# schematic.net
KiCad netlist of a schematic drawn in Altium Designer
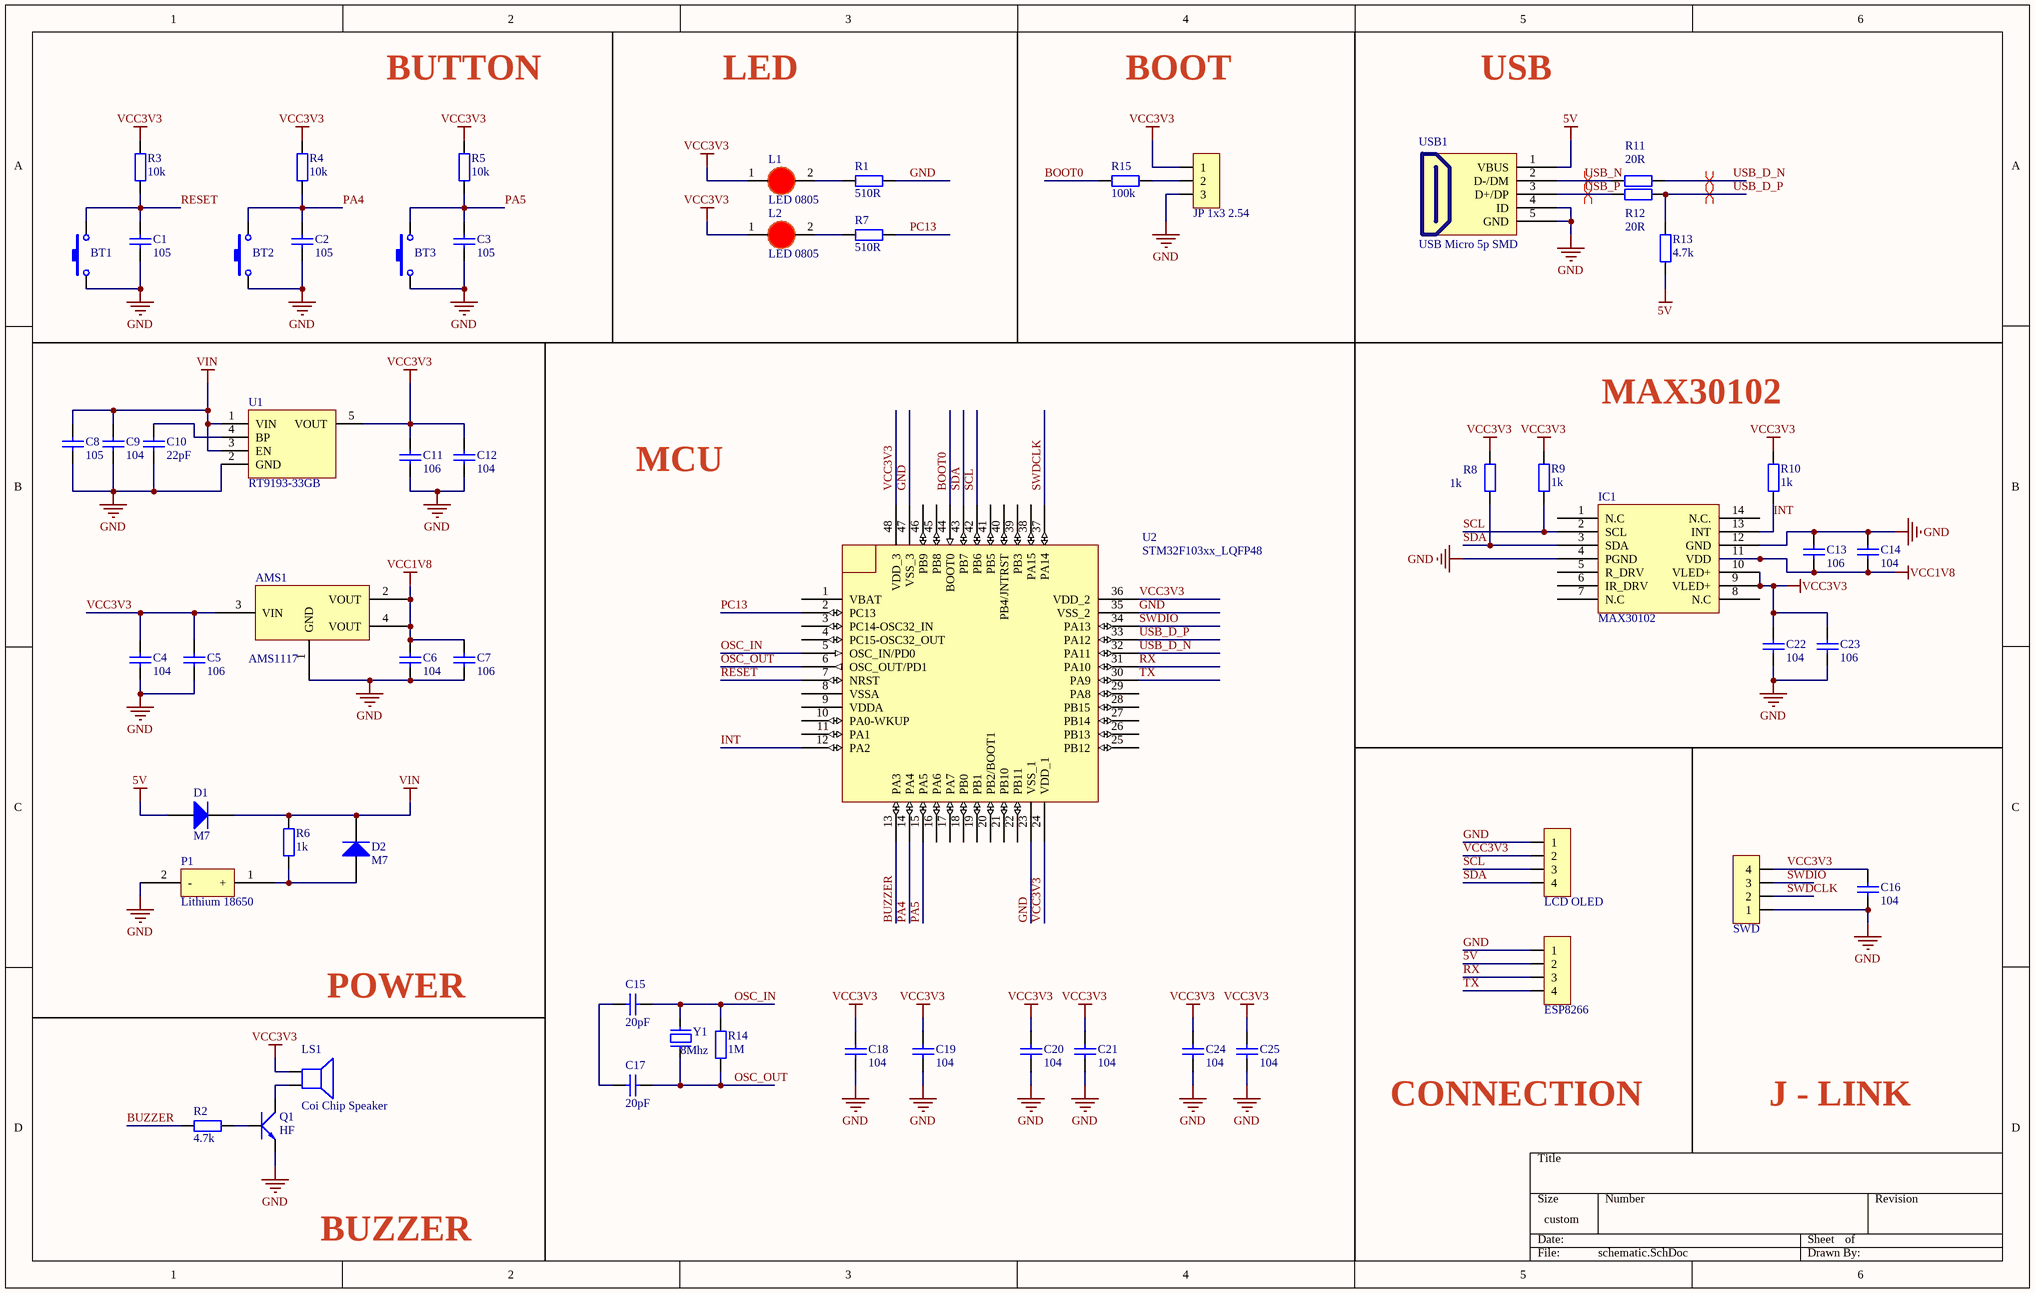
[diagram p0: schematic.SchDoc]

(export (version "E")
  (design (tool "Eeschema 10.0.6"))
  (components
    (comp (ref "AMS1")
      (value "AMS1117")
      (footprint "SOT223")
      (description "Dán")
      (libsource (lib "Altium_Lib_by_KhueNguyenCreator") (part "AMS1117 SMD"))
    )
    (comp (ref "BT1")
      (value "Nut Nhan 2 Chan SMD 3x6x2.5")
      (footprint "Nut Nhan 2 Chan SMD 3x6x2.5")
      (libsource (lib "Altium_Lib_by_KhueNguyenCreator") (part "Nut Nhan 2 Chan SMD 3x6x2.5"))
    )
    (comp (ref "BT2")
      (value "Nut Nhan 2 Chan SMD 3x6x2.5")
      (footprint "Nut Nhan 2 Chan SMD 3x6x2.5")
      (libsource (lib "Altium_Lib_by_KhueNguyenCreator") (part "Nut Nhan 2 Chan SMD 3x6x2.5"))
    )
    (comp (ref "BT3")
      (value "Nut Nhan 2 Chan SMD 3x6x2.5")
      (footprint "Nut Nhan 2 Chan SMD 3x6x2.5")
      (libsource (lib "Altium_Lib_by_KhueNguyenCreator") (part "Nut Nhan 2 Chan SMD 3x6x2.5"))
    )
    (comp (ref "C1")
      (value "105")
      (footprint "tu 0603")
      (description "Dán")
      (libsource (lib "Altium_Lib_by_KhueNguyenCreator") (part "Tu 0603 105 50V 10%"))
    )
    (comp (ref "C2")
      (value "105")
      (footprint "tu 0603")
      (description "Dán")
      (libsource (lib "Altium_Lib_by_KhueNguyenCreator") (part "Tu 0603 105 50V 10%"))
    )
    (comp (ref "C3")
      (value "105")
      (footprint "tu 0603")
      (description "Dán")
      (libsource (lib "Altium_Lib_by_KhueNguyenCreator") (part "Tu 0603 105 50V 10%"))
    )
    (comp (ref "C4")
      (value "104")
      (footprint "tu 0603")
      (description "Dán")
      (libsource (lib "Altium_Lib_by_KhueNguyenCreator") (part "Tu 0603 104 50V 10%"))
    )
    (comp (ref "C5")
      (value "106")
      (footprint "tu 0603")
      (description "Dán")
      (libsource (lib "Altium_Lib_by_KhueNguyenCreator") (part "Tu 0603 106 16V 20%"))
    )
    (comp (ref "C6")
      (value "104")
      (footprint "tu 0603")
      (description "Dán")
      (libsource (lib "Altium_Lib_by_KhueNguyenCreator") (part "Tu 0603 104 50V 10%"))
    )
    (comp (ref "C7")
      (value "106")
      (footprint "tu 0603")
      (description "Dán")
      (libsource (lib "Altium_Lib_by_KhueNguyenCreator") (part "Tu 0603 106 16V 20%"))
    )
    (comp (ref "C8")
      (value "105")
      (footprint "tu 0603")
      (description "Dán")
      (libsource (lib "Altium_Lib_by_KhueNguyenCreator") (part "Tu 0603 105 16V 20%"))
    )
    (comp (ref "C9")
      (value "104")
      (footprint "tu 0603")
      (description "Dán")
      (libsource (lib "Altium_Lib_by_KhueNguyenCreator") (part "Tu 0603 104 50V 10%"))
    )
    (comp (ref "C10")
      (value "22pF")
      (footprint "tu 0603")
      (description "Dán")
      (libsource (lib "Altium_Lib_by_KhueNguyenCreator") (part "Tu 0603 22pF 50V 10%"))
    )
    (comp (ref "C11")
      (value "106")
      (footprint "tu 0603")
      (description "Dán")
      (libsource (lib "Altium_Lib_by_KhueNguyenCreator") (part "Tu 0603 106 16V 20%"))
    )
    (comp (ref "C12")
      (value "104")
      (footprint "tu 0603")
      (description "Dán")
      (libsource (lib "Altium_Lib_by_KhueNguyenCreator") (part "Tu 0603 104 50V 10%"))
    )
    (comp (ref "C13")
      (value "106")
      (footprint "tu 0603")
      (description "Dán")
      (libsource (lib "Altium_Lib_by_KhueNguyenCreator") (part "Tu 0603 106 16V 20%"))
    )
    (comp (ref "C14")
      (value "104")
      (footprint "tu 0603")
      (description "Dán")
      (libsource (lib "Altium_Lib_by_KhueNguyenCreator") (part "Tu 0603 104 50V 10%"))
    )
    (comp (ref "C15")
      (value "20pF")
      (footprint "tu 0805")
      (description "Dán")
      (libsource (lib "Altium_Lib_by_KhueNguyenCreator") (part "Tu 0805 20pF 50V 10%"))
    )
    (comp (ref "C16")
      (value "104")
      (footprint "tu 0603")
      (description "Dán")
      (libsource (lib "Altium_Lib_by_KhueNguyenCreator") (part "Tu 0603 104 50V 10%"))
    )
    (comp (ref "C17")
      (value "20pF")
      (footprint "tu 0805")
      (description "Dán")
      (libsource (lib "Altium_Lib_by_KhueNguyenCreator") (part "Tu 0805 20pF 50V 10%"))
    )
    (comp (ref "C18")
      (value "104")
      (footprint "tu 0603")
      (description "Dán")
      (libsource (lib "Altium_Lib_by_KhueNguyenCreator") (part "Tu 0603 104 50V 10%"))
    )
    (comp (ref "C19")
      (value "104")
      (footprint "tu 0603")
      (description "Dán")
      (libsource (lib "Altium_Lib_by_KhueNguyenCreator") (part "Tu 0603 104 50V 10%"))
    )
    (comp (ref "C20")
      (value "104")
      (footprint "tu 0603")
      (description "Dán")
      (libsource (lib "Altium_Lib_by_KhueNguyenCreator") (part "Tu 0603 104 50V 10%"))
    )
    (comp (ref "C21")
      (value "104")
      (footprint "tu 0603")
      (description "Dán")
      (libsource (lib "Altium_Lib_by_KhueNguyenCreator") (part "Tu 0603 104 50V 10%"))
    )
    (comp (ref "C22")
      (value "104")
      (footprint "tu 0603")
      (description "Dán")
      (libsource (lib "Altium_Lib_by_KhueNguyenCreator") (part "Tu 0603 104 50V 10%"))
    )
    (comp (ref "C23")
      (value "106")
      (footprint "tu 0603")
      (description "Dán")
      (libsource (lib "Altium_Lib_by_KhueNguyenCreator") (part "Tu 0603 106 16V 20%"))
    )
    (comp (ref "C24")
      (value "104")
      (footprint "tu 0603")
      (description "Dán")
      (libsource (lib "Altium_Lib_by_KhueNguyenCreator") (part "Tu 0603 104 50V 10%"))
    )
    (comp (ref "C25")
      (value "104")
      (footprint "tu 0603")
      (description "Dán")
      (libsource (lib "Altium_Lib_by_KhueNguyenCreator") (part "Tu 0603 104 50V 10%"))
    )
    (comp (ref "D1")
      (value "M7")
      (footprint "DIODE SMA")
      (description "Dán")
      (libsource (lib "Altium_Lib_by_KhueNguyenCreator") (part "Diode M7 ( 4007 )"))
    )
    (comp (ref "D2")
      (value "M7")
      (footprint "DIODE SMA")
      (description "Dán")
      (libsource (lib "Altium_Lib_by_KhueNguyenCreator") (part "Diode M7 ( 4007 )"))
    )
    (comp (ref "IC1") (value "MAX30102") (footprint "Max30102") (libsource (lib "MyLib") (part "MAX30102")))
    (comp (ref "JP1")
      (value "SWD")
      (footprint "JP 1x4 DT")
      (description "Cắm")
      (libsource (lib "") (part "JP 1x4 2.54 Duc Thang_1"))
    )
    (comp (ref "JP2")
      (value "LCD OLED")
      (footprint "JP 1x4 DT")
      (description "Cắm")
      (libsource (lib "Altium_Lib_by_KhueNguyenCreator") (part "JP 1x4 2.54 Duc Thang"))
    )
    (comp (ref "JP3")
      (value "JP 1x3 2.54")
      (footprint "JP 1x3 DT")
      (description "Cắm")
      (libsource (lib "Altium_Lib_by_KhueNguyenCreator") (part "JP 1x3 2.54 Duc Thang"))
    )
    (comp (ref "JP4")
      (value "ESP8266")
      (footprint "JP 1x4 DT")
      (description "Cắm")
      (libsource (lib "Altium_Lib_by_KhueNguyenCreator") (part "JP 1x4 2.54 Duc Thang"))
    )
    (comp (ref "L1")
      (value "LED 0805")
      (footprint "LED-0805-Red")
      (description "Dán")
      (libsource (lib "Altium_Lib_by_KhueNguyenCreator") (part "LED 0805 Do"))
    )
    (comp (ref "L2")
      (value "LED 0805")
      (footprint "LED-0805-Red")
      (description "Dán")
      (libsource (lib "Altium_Lib_by_KhueNguyenCreator") (part "LED 0805 Do"))
    )
    (comp (ref "LS1")
      (value "Coi Chip Speaker")
      (footprint "Coi Chip Speacker")
      (description "Còi chip")
      (libsource (lib "Altium_Lib_by_KhueNguyenCreator") (part "Coi Chip Speaker"))
    )
    (comp (ref "P1")
      (value "Lithium 18650")
      (footprint "18650_Lithium")
      (libsource (lib "MyLib") (part "Lithium 18650"))
    )
    (comp (ref "Q1")
      (value "HF")
      (footprint "SOT-23")
      (description "SOT-23")
      (libsource (lib "Altium_Lib_by_KhueNguyenCreator") (part "Trans C1815 HF SMD"))
    )
    (comp (ref "R1")
      (value "510R")
      (footprint "tro smd 0603")
      (description "Dán")
      (libsource (lib "Altium_Lib_by_KhueNguyenCreator") (part "Tro 0603 5% 510R"))
    )
    (comp (ref "R2")
      (value "4.7k")
      (footprint "tro smd 0603")
      (description "Dán")
      (libsource (lib "Altium_Lib_by_KhueNguyenCreator") (part "Tro 0603 5% 4.7k"))
    )
    (comp (ref "R3")
      (value "10k")
      (footprint "tro smd 0603")
      (description "Dán")
      (libsource (lib "Altium_Lib_by_KhueNguyenCreator") (part "Tro 0603 1% 10k"))
    )
    (comp (ref "R4")
      (value "10k")
      (footprint "tro smd 0603")
      (description "Dán")
      (libsource (lib "Altium_Lib_by_KhueNguyenCreator") (part "Tro 0603 1% 10k"))
    )
    (comp (ref "R5")
      (value "10k")
      (footprint "tro smd 0603")
      (description "Dán")
      (libsource (lib "Altium_Lib_by_KhueNguyenCreator") (part "Tro 0603 1% 10k"))
    )
    (comp (ref "R6")
      (value "1k")
      (footprint "tro smd 0603")
      (description "Dán")
      (libsource (lib "Altium_Lib_by_KhueNguyenCreator") (part "Tro 0603 5% 1k"))
    )
    (comp (ref "R7")
      (value "510R")
      (footprint "tro smd 0603")
      (description "Dán")
      (libsource (lib "Altium_Lib_by_KhueNguyenCreator") (part "Tro 0603 5% 510R"))
    )
    (comp (ref "R8")
      (value "1k")
      (footprint "tro smd 0603")
      (description "Dán")
      (libsource (lib "Altium_Lib_by_KhueNguyenCreator") (part "Tro 0603 5% 4.7k"))
    )
    (comp (ref "R9")
      (value "1k")
      (footprint "tro smd 0603")
      (description "Dán")
      (libsource (lib "Altium_Lib_by_KhueNguyenCreator") (part "Tro 0603 5% 4.7k"))
    )
    (comp (ref "R10")
      (value "1k")
      (footprint "tro smd 0603")
      (description "Dán")
      (libsource (lib "Altium_Lib_by_KhueNguyenCreator") (part "Tro 0603 5% 4.7k"))
    )
    (comp (ref "R11")
      (value "20R")
      (footprint "tro smd 0603")
      (description "Dán")
      (libsource (lib "Altium_Lib_by_KhueNguyenCreator") (part "Tro 0603 5% 22R"))
    )
    (comp (ref "R12")
      (value "20R")
      (footprint "tro smd 0603")
      (description "Dán")
      (libsource (lib "Altium_Lib_by_KhueNguyenCreator") (part "Tro 0603 5% 22R"))
    )
    (comp (ref "R13")
      (value "4.7k")
      (footprint "tro smd 0603")
      (description "Dán")
      (libsource (lib "Altium_Lib_by_KhueNguyenCreator") (part "Tro 0603 5% 4.7k"))
    )
    (comp (ref "R14")
      (value "1M")
      (footprint "tro smd 0603")
      (description "Dán")
      (libsource (lib "Altium_Lib_by_KhueNguyenCreator") (part "Tro 0603 5% 1M"))
    )
    (comp (ref "R15")
      (value "100k")
      (footprint "tro smd 0603")
      (description "Dán")
      (libsource (lib "Altium_Lib_by_KhueNguyenCreator") (part "Tro 0603 5% 100k"))
    )
    (comp (ref "U1")
      (value "RT9193-33GB")
      (footprint "SOT23-5")
      (description "Linear Voltage Regulator IC 1 Output 300mA SOT-23-5")
      (fields (field (name "MANUFACTURER") "Richtek USA Inc."))
      (libsource (lib "Altium_Lib_by_KhueNguyenCreator") (part "REG_5.5V-3.3V-0.3A-1W-SOT-23-5"))
    )
    (comp (ref "U2")
      (value "STM32F103xx_LQFP48")
      (footprint "STM32_LQPF48")
      (fields (field (name "PUBLISHER") "Altium Limited"))
      (libsource (lib "Altium_Lib_by_KhueNguyenCreator") (part "STM32F103xx_LQFP48"))
    )
    (comp (ref "USB1")
      (value "USB Micro 5p SMD")
      (footprint "USB Micro 5p SMD")
      (description "USB Type B")
      (libsource (lib "Altium_Lib_by_KhueNguyenCreator") (part "USB Micro 5p SMD"))
    )
    (comp (ref "Y1")
      (value "8Mhz")
      (footprint "Thach Anh 2 chan SMD5032")
      (description "Crystal For all Crystal 2pin.")
      (libsource (lib "Altium_Lib_by_KhueNguyenCreator") (part "Thach Anh 2 chan SMD 5032"))
    )
  )
  (nets
    (net (code "1") (name "/BOOT0") (class "Default")
      (node (ref "R15") (pin "1") (pinfunction "1_1") (pintype "passive"))
      (node (ref "U2") (pin "44") (pinfunction "BOOT0_44") (pintype "input"))
    )
    (net (code "2") (name "/BUZZER") (class "Default")
      (node (ref "R2") (pin "1") (pinfunction "1_1") (pintype "passive"))
      (node (ref "U2") (pin "13") (pinfunction "PA3_13") (pintype "bidirectional"))
    )
    (net (code "3") (name "/INT") (class "Default")
      (node (ref "IC1") (pin "13") (pinfunction "INT_13") (pintype "passive"))
      (node (ref "R10") (pin "2") (pinfunction "2_2") (pintype "passive"))
      (node (ref "U2") (pin "12") (pinfunction "PA2_12") (pintype "bidirectional"))
    )
    (net (code "4") (name "/OSC_IN") (class "Default")
      (node (ref "C15") (pin "1") (pinfunction "1_1") (pintype "passive"))
      (node (ref "R14") (pin "2") (pinfunction "2_2") (pintype "passive"))
      (node (ref "U2") (pin "5") (pinfunction "OSC_IN/PD0_5") (pintype "input"))
      (node (ref "Y1") (pin "2") (pinfunction "2_2") (pintype "passive"))
    )
    (net (code "5") (name "/OSC_OUT") (class "Default")
      (node (ref "C17") (pin "1") (pinfunction "1_1") (pintype "passive"))
      (node (ref "R14") (pin "1") (pinfunction "1_1") (pintype "passive"))
      (node (ref "U2") (pin "6") (pinfunction "OSC_OUT/PD1_6") (pintype "output"))
      (node (ref "Y1") (pin "1") (pinfunction "1_1") (pintype "passive"))
    )
    (net (code "6") (name "/PA4") (class "Default")
      (node (ref "BT2") (pin "2") (pinfunction "2_2") (pintype "passive"))
      (node (ref "C2") (pin "1") (pinfunction "1_1") (pintype "passive"))
      (node (ref "R4") (pin "1") (pinfunction "1_1") (pintype "passive"))
      (node (ref "U2") (pin "14") (pinfunction "PA4_14") (pintype "bidirectional"))
    )
    (net (code "7") (name "/PA5") (class "Default")
      (node (ref "BT3") (pin "2") (pinfunction "2_2") (pintype "passive"))
      (node (ref "C3") (pin "1") (pinfunction "1_1") (pintype "passive"))
      (node (ref "R5") (pin "1") (pinfunction "1_1") (pintype "passive"))
      (node (ref "U2") (pin "15") (pinfunction "PA5_15") (pintype "bidirectional"))
    )
    (net (code "8") (name "/PC13") (class "Default")
      (node (ref "R7") (pin "2") (pinfunction "2_2") (pintype "passive"))
      (node (ref "U2") (pin "2") (pinfunction "PC13_2") (pintype "bidirectional"))
    )
    (net (code "9") (name "/RESET") (class "Default")
      (node (ref "BT1") (pin "2") (pinfunction "2_2") (pintype "passive"))
      (node (ref "C1") (pin "1") (pinfunction "1_1") (pintype "passive"))
      (node (ref "R3") (pin "1") (pinfunction "1_1") (pintype "passive"))
      (node (ref "U2") (pin "7") (pinfunction "NRST_7") (pintype "bidirectional"))
    )
    (net (code "10") (name "/RX") (class "Default")
      (node (ref "JP4") (pin "3") (pinfunction "3_3") (pintype "passive"))
      (node (ref "U2") (pin "31") (pinfunction "PA10_31") (pintype "bidirectional"))
    )
    (net (code "11") (name "/SCL") (class "Default")
      (node (ref "IC1") (pin "2") (pinfunction "SCL_2") (pintype "passive"))
      (node (ref "JP2") (pin "3") (pinfunction "3_3") (pintype "passive"))
      (node (ref "R9") (pin "2") (pinfunction "2_2") (pintype "passive"))
      (node (ref "U2") (pin "42") (pinfunction "PB6_42") (pintype "bidirectional"))
    )
    (net (code "12") (name "/SDA") (class "Default")
      (node (ref "IC1") (pin "3") (pinfunction "SDA_3") (pintype "passive"))
      (node (ref "JP2") (pin "4") (pinfunction "4_4") (pintype "passive"))
      (node (ref "R8") (pin "1") (pinfunction "1_1") (pintype "passive"))
      (node (ref "U2") (pin "43") (pinfunction "PB7_43") (pintype "bidirectional"))
    )
    (net (code "13") (name "/SWDCLK") (class "Default")
      (node (ref "JP1") (pin "2") (pinfunction "2_2") (pintype "passive"))
      (node (ref "U2") (pin "37") (pinfunction "PA14_37") (pintype "bidirectional"))
    )
    (net (code "14") (name "/SWDIO") (class "Default")
      (node (ref "JP1") (pin "3") (pinfunction "3_3") (pintype "passive"))
      (node (ref "U2") (pin "34") (pinfunction "PA13_34") (pintype "bidirectional"))
    )
    (net (code "15") (name "/TX") (class "Default")
      (node (ref "JP4") (pin "4") (pinfunction "4_4") (pintype "passive"))
      (node (ref "U2") (pin "30") (pinfunction "PA9_30") (pintype "bidirectional"))
    )
    (net (code "16") (name "/USB_D_N") (class "Default")
      (node (ref "R11") (pin "2") (pinfunction "2_2") (pintype "passive"))
      (node (ref "U2") (pin "32") (pinfunction "PA11_32") (pintype "bidirectional"))
    )
    (net (code "17") (name "/USB_D_P") (class "Default")
      (node (ref "R12") (pin "2") (pinfunction "2_2") (pintype "passive"))
      (node (ref "R13") (pin "2") (pinfunction "2_2") (pintype "passive"))
      (node (ref "U2") (pin "33") (pinfunction "PA12_33") (pintype "bidirectional"))
    )
    (net (code "18") (name "/USB_N") (class "Default")
      (node (ref "R11") (pin "1") (pinfunction "1_1") (pintype "passive"))
      (node (ref "USB1") (pin "2") (pinfunction "D-/DM_2") (pintype "passive"))
    )
    (net (code "19") (name "/USB_P") (class "Default")
      (node (ref "R12") (pin "1") (pinfunction "1_1") (pintype "passive"))
      (node (ref "USB1") (pin "3") (pinfunction "D+/DP_3") (pintype "passive"))
    )
    (net (code "20") (name "5V") (class "Default")
      (node (ref "D1") (pin "1") (pinfunction "A_1") (pintype "passive"))
      (node (ref "JP4") (pin "2") (pinfunction "2_2") (pintype "passive"))
      (node (ref "R13") (pin "1") (pinfunction "1_1") (pintype "passive"))
      (node (ref "USB1") (pin "1") (pinfunction "VBUS_1") (pintype "passive"))
    )
    (net (code "21") (name "GND") (class "Default")
      (node (ref "AMS1") (pin "1") (pinfunction "GND_1") (pintype "passive"))
      (node (ref "BT1") (pin "1") (pinfunction "1_1") (pintype "passive"))
      (node (ref "BT2") (pin "1") (pinfunction "1_1") (pintype "passive"))
      (node (ref "BT3") (pin "1") (pinfunction "1_1") (pintype "passive"))
      (node (ref "C1") (pin "2") (pinfunction "2_2") (pintype "passive"))
      (node (ref "C10") (pin "2") (pinfunction "2_2") (pintype "passive"))
      (node (ref "C11") (pin "2") (pinfunction "2_2") (pintype "passive"))
      (node (ref "C12") (pin "2") (pinfunction "2_2") (pintype "passive"))
      (node (ref "C13") (pin "1") (pinfunction "1_1") (pintype "passive"))
      (node (ref "C14") (pin "1") (pinfunction "1_1") (pintype "passive"))
      (node (ref "C16") (pin "2") (pinfunction "2_2") (pintype "passive"))
      (node (ref "C18") (pin "2") (pinfunction "2_2") (pintype "passive"))
      (node (ref "C19") (pin "2") (pinfunction "2_2") (pintype "passive"))
      (node (ref "C2") (pin "2") (pinfunction "2_2") (pintype "passive"))
      (node (ref "C20") (pin "2") (pinfunction "2_2") (pintype "passive"))
      (node (ref "C21") (pin "2") (pinfunction "2_2") (pintype "passive"))
      (node (ref "C22") (pin "1") (pinfunction "1_1") (pintype "passive"))
      (node (ref "C23") (pin "1") (pinfunction "1_1") (pintype "passive"))
      (node (ref "C24") (pin "2") (pinfunction "2_2") (pintype "passive"))
      (node (ref "C25") (pin "2") (pinfunction "2_2") (pintype "passive"))
      (node (ref "C3") (pin "2") (pinfunction "2_2") (pintype "passive"))
      (node (ref "C4") (pin "1") (pinfunction "1_1") (pintype "passive"))
      (node (ref "C5") (pin "1") (pinfunction "1_1") (pintype "passive"))
      (node (ref "C6") (pin "1") (pinfunction "1_1") (pintype "passive"))
      (node (ref "C7") (pin "1") (pinfunction "1_1") (pintype "passive"))
      (node (ref "C8") (pin "2") (pinfunction "2_2") (pintype "passive"))
      (node (ref "C9") (pin "2") (pinfunction "2_2") (pintype "passive"))
      (node (ref "IC1") (pin "12") (pinfunction "GND_12") (pintype "passive"))
      (node (ref "IC1") (pin "4") (pinfunction "PGND_4") (pintype "passive"))
      (node (ref "JP1") (pin "1") (pinfunction "1_1") (pintype "passive"))
      (node (ref "JP2") (pin "1") (pinfunction "1_1") (pintype "passive"))
      (node (ref "JP3") (pin "3") (pinfunction "3_3") (pintype "passive"))
      (node (ref "JP4") (pin "1") (pinfunction "1_1") (pintype "passive"))
      (node (ref "P1") (pin "2") (pinfunction "-_2") (pintype "power_in"))
      (node (ref "Q1") (pin "2") (pinfunction "E_2") (pintype "passive"))
      (node (ref "R1") (pin "2") (pinfunction "2_2") (pintype "passive"))
      (node (ref "U1") (pin "2") (pinfunction "GND_2") (pintype "passive"))
      (node (ref "U2") (pin "23") (pinfunction "VSS_1_23") (pintype "power_in"))
      (node (ref "U2") (pin "35") (pinfunction "VSS_2_35") (pintype "power_in"))
      (node (ref "U2") (pin "47") (pinfunction "VSS_3_47") (pintype "power_in"))
      (node (ref "USB1") (pin "4") (pinfunction "ID_4") (pintype "passive"))
      (node (ref "USB1") (pin "5") (pinfunction "GND_5") (pintype "passive"))
    )
    (net (code "22") (name "Net-(C15-Pad2)") (class "Default")
      (node (ref "C15") (pin "2") (pinfunction "2_2") (pintype "passive"))
      (node (ref "C17") (pin "2") (pinfunction "2_2") (pintype "passive"))
    )
    (net (code "23") (name "Net-(D2-A)") (class "Default")
      (node (ref "D2") (pin "1") (pinfunction "A_1") (pintype "passive"))
      (node (ref "P1") (pin "1") (pinfunction "+_1") (pintype "passive"))
      (node (ref "R6") (pin "1") (pinfunction "1_1") (pintype "passive"))
    )
    (net (code "24") (name "Net-(JP3-Pad2)") (class "Default")
      (node (ref "JP3") (pin "2") (pinfunction "2_2") (pintype "passive"))
      (node (ref "R15") (pin "2") (pinfunction "2_2") (pintype "passive"))
    )
    (net (code "25") (name "Net-(L1-K)") (class "Default")
      (node (ref "L1") (pin "2") (pinfunction "K_2") (pintype "passive"))
      (node (ref "R1") (pin "1") (pinfunction "1_1") (pintype "passive"))
    )
    (net (code "26") (name "Net-(L2-K)") (class "Default")
      (node (ref "L2") (pin "2") (pinfunction "K_2") (pintype "passive"))
      (node (ref "R7") (pin "1") (pinfunction "1_1") (pintype "passive"))
    )
    (net (code "27") (name "Net-(Q1-B)") (class "Default")
      (node (ref "Q1") (pin "1") (pinfunction "B_1") (pintype "passive"))
      (node (ref "R2") (pin "2") (pinfunction "2_2") (pintype "passive"))
    )
    (net (code "28") (name "Net-(Q1-C)") (class "Default")
      (node (ref "LS1") (pin "2") (pinfunction "2_2") (pintype "passive"))
      (node (ref "Q1") (pin "3") (pinfunction "C_3") (pintype "passive"))
    )
    (net (code "29") (name "Net-(U1-BP)") (class "Default")
      (node (ref "C10") (pin "1") (pinfunction "1_1") (pintype "passive"))
      (node (ref "U1") (pin "4") (pinfunction "BP_4") (pintype "passive"))
    )
    (net (code "30") (name "VCC1V8") (class "Default")
      (node (ref "AMS1") (pin "2") (pinfunction "VOUT_2") (pintype "passive"))
      (node (ref "AMS1") (pin "4") (pinfunction "VOUT_4") (pintype "passive"))
      (node (ref "C13") (pin "2") (pinfunction "2_2") (pintype "passive"))
      (node (ref "C14") (pin "2") (pinfunction "2_2") (pintype "passive"))
      (node (ref "C6") (pin "2") (pinfunction "2_2") (pintype "passive"))
      (node (ref "C7") (pin "2") (pinfunction "2_2") (pintype "passive"))
      (node (ref "IC1") (pin "11") (pinfunction "VDD_11") (pintype "passive"))
    )
    (net (code "31") (name "VCC3V3") (class "Default")
      (node (ref "AMS1") (pin "3") (pinfunction "VIN_3") (pintype "passive"))
      (node (ref "C11") (pin "1") (pinfunction "1_1") (pintype "passive"))
      (node (ref "C12") (pin "1") (pinfunction "1_1") (pintype "passive"))
      (node (ref "C16") (pin "1") (pinfunction "1_1") (pintype "passive"))
      (node (ref "C18") (pin "1") (pinfunction "1_1") (pintype "passive"))
      (node (ref "C19") (pin "1") (pinfunction "1_1") (pintype "passive"))
      (node (ref "C20") (pin "1") (pinfunction "1_1") (pintype "passive"))
      (node (ref "C21") (pin "1") (pinfunction "1_1") (pintype "passive"))
      (node (ref "C22") (pin "2") (pinfunction "2_2") (pintype "passive"))
      (node (ref "C23") (pin "2") (pinfunction "2_2") (pintype "passive"))
      (node (ref "C24") (pin "1") (pinfunction "1_1") (pintype "passive"))
      (node (ref "C25") (pin "1") (pinfunction "1_1") (pintype "passive"))
      (node (ref "C4") (pin "2") (pinfunction "2_2") (pintype "passive"))
      (node (ref "C5") (pin "2") (pinfunction "2_2") (pintype "passive"))
      (node (ref "IC1") (pin "10") (pinfunction "VLED+_10") (pintype "passive"))
      (node (ref "IC1") (pin "9") (pinfunction "VLED+_9") (pintype "passive"))
      (node (ref "JP1") (pin "4") (pinfunction "4_4") (pintype "passive"))
      (node (ref "JP2") (pin "2") (pinfunction "2_2") (pintype "passive"))
      (node (ref "JP3") (pin "1") (pinfunction "1_1") (pintype "passive"))
      (node (ref "L1") (pin "1") (pinfunction "A_1") (pintype "passive"))
      (node (ref "L2") (pin "1") (pinfunction "A_1") (pintype "passive"))
      (node (ref "LS1") (pin "1") (pinfunction "1_1") (pintype "passive"))
      (node (ref "R10") (pin "1") (pinfunction "1_1") (pintype "passive"))
      (node (ref "R3") (pin "2") (pinfunction "2_2") (pintype "passive"))
      (node (ref "R4") (pin "2") (pinfunction "2_2") (pintype "passive"))
      (node (ref "R5") (pin "2") (pinfunction "2_2") (pintype "passive"))
      (node (ref "R8") (pin "2") (pinfunction "2_2") (pintype "passive"))
      (node (ref "R9") (pin "1") (pinfunction "1_1") (pintype "passive"))
      (node (ref "U1") (pin "5") (pinfunction "VOUT_5") (pintype "passive"))
      (node (ref "U2") (pin "24") (pinfunction "VDD_1_24") (pintype "power_in"))
      (node (ref "U2") (pin "36") (pinfunction "VDD_2_36") (pintype "power_in"))
      (node (ref "U2") (pin "48") (pinfunction "VDD_3_48") (pintype "power_in"))
    )
    (net (code "32") (name "VIN") (class "Default")
      (node (ref "C8") (pin "1") (pinfunction "1_1") (pintype "passive"))
      (node (ref "C9") (pin "1") (pinfunction "1_1") (pintype "passive"))
      (node (ref "D1") (pin "2") (pinfunction "K_2") (pintype "passive"))
      (node (ref "D2") (pin "2") (pinfunction "K_2") (pintype "passive"))
      (node (ref "R6") (pin "2") (pinfunction "2_2") (pintype "passive"))
      (node (ref "U1") (pin "1") (pinfunction "VIN_1") (pintype "passive"))
      (node (ref "U1") (pin "3") (pinfunction "EN_3") (pintype "passive"))
    )
    (net (code "33") (name "unconnected-(IC1-IR_DRV-Pad6)") (class "Default")
      (node (ref "IC1") (pin "6") (pinfunction "IR_DRV_6") (pintype "passive"))
    )
    (net (code "34") (name "unconnected-(IC1-N.C-Pad1)") (class "Default")
      (node (ref "IC1") (pin "1") (pinfunction "N.C_1") (pintype "passive"))
    )
    (net (code "35") (name "unconnected-(IC1-N.C-Pad7)") (class "Default")
      (node (ref "IC1") (pin "7") (pinfunction "N.C_7") (pintype "passive"))
    )
    (net (code "36") (name "unconnected-(IC1-N.C-Pad8)") (class "Default")
      (node (ref "IC1") (pin "8") (pinfunction "N.C_8") (pintype "passive"))
    )
    (net (code "37") (name "unconnected-(IC1-N.C.-Pad14)") (class "Default")
      (node (ref "IC1") (pin "14") (pinfunction "N.C._14") (pintype "passive"))
    )
    (net (code "38") (name "unconnected-(IC1-R_DRV-Pad5)") (class "Default")
      (node (ref "IC1") (pin "5") (pinfunction "R_DRV_5") (pintype "passive"))
    )
    (net (code "39") (name "unconnected-(U2-PA0-WKUP-Pad10)") (class "Default")
      (node (ref "U2") (pin "10") (pinfunction "PA0-WKUP_10") (pintype "bidirectional"))
    )
    (net (code "40") (name "unconnected-(U2-PA1-Pad11)") (class "Default")
      (node (ref "U2") (pin "11") (pinfunction "PA1_11") (pintype "bidirectional"))
    )
    (net (code "41") (name "unconnected-(U2-PA6-Pad16)") (class "Default")
      (node (ref "U2") (pin "16") (pinfunction "PA6_16") (pintype "bidirectional"))
    )
    (net (code "42") (name "unconnected-(U2-PA7-Pad17)") (class "Default")
      (node (ref "U2") (pin "17") (pinfunction "PA7_17") (pintype "bidirectional"))
    )
    (net (code "43") (name "unconnected-(U2-PA8-Pad29)") (class "Default")
      (node (ref "U2") (pin "29") (pinfunction "PA8_29") (pintype "bidirectional"))
    )
    (net (code "44") (name "unconnected-(U2-PA15-Pad38)") (class "Default")
      (node (ref "U2") (pin "38") (pinfunction "PA15_38") (pintype "bidirectional"))
    )
    (net (code "45") (name "unconnected-(U2-PB0-Pad18)") (class "Default")
      (node (ref "U2") (pin "18") (pinfunction "PB0_18") (pintype "bidirectional"))
    )
    (net (code "46") (name "unconnected-(U2-PB1-Pad19)") (class "Default")
      (node (ref "U2") (pin "19") (pinfunction "PB1_19") (pintype "bidirectional"))
    )
    (net (code "47") (name "unconnected-(U2-PB2{slash}BOOT1-Pad20)") (class "Default")
      (node (ref "U2") (pin "20") (pinfunction "PB2/BOOT1_20") (pintype "bidirectional"))
    )
    (net (code "48") (name "unconnected-(U2-PB3-Pad39)") (class "Default")
      (node (ref "U2") (pin "39") (pinfunction "PB3_39") (pintype "bidirectional"))
    )
    (net (code "49") (name "unconnected-(U2-PB4{slash}JNTRST-Pad40)") (class "Default")
      (node (ref "U2") (pin "40") (pinfunction "PB4/JNTRST_40") (pintype "bidirectional"))
    )
    (net (code "50") (name "unconnected-(U2-PB5-Pad41)") (class "Default")
      (node (ref "U2") (pin "41") (pinfunction "PB5_41") (pintype "bidirectional"))
    )
    (net (code "51") (name "unconnected-(U2-PB8-Pad45)") (class "Default")
      (node (ref "U2") (pin "45") (pinfunction "PB8_45") (pintype "bidirectional"))
    )
    (net (code "52") (name "unconnected-(U2-PB9-Pad46)") (class "Default")
      (node (ref "U2") (pin "46") (pinfunction "PB9_46") (pintype "bidirectional"))
    )
    (net (code "53") (name "unconnected-(U2-PB10-Pad21)") (class "Default")
      (node (ref "U2") (pin "21") (pinfunction "PB10_21") (pintype "bidirectional"))
    )
    (net (code "54") (name "unconnected-(U2-PB11-Pad22)") (class "Default")
      (node (ref "U2") (pin "22") (pinfunction "PB11_22") (pintype "bidirectional"))
    )
    (net (code "55") (name "unconnected-(U2-PB12-Pad25)") (class "Default")
      (node (ref "U2") (pin "25") (pinfunction "PB12_25") (pintype "bidirectional"))
    )
    (net (code "56") (name "unconnected-(U2-PB13-Pad26)") (class "Default")
      (node (ref "U2") (pin "26") (pinfunction "PB13_26") (pintype "bidirectional"))
    )
    (net (code "57") (name "unconnected-(U2-PB14-Pad27)") (class "Default")
      (node (ref "U2") (pin "27") (pinfunction "PB14_27") (pintype "bidirectional"))
    )
    (net (code "58") (name "unconnected-(U2-PB15-Pad28)") (class "Default")
      (node (ref "U2") (pin "28") (pinfunction "PB15_28") (pintype "bidirectional"))
    )
    (net (code "59") (name "unconnected-(U2-PC14-OSC32_IN-Pad3)") (class "Default")
      (node (ref "U2") (pin "3") (pinfunction "PC14-OSC32_IN_3") (pintype "bidirectional"))
    )
    (net (code "60") (name "unconnected-(U2-PC15-OSC32_OUT-Pad4)") (class "Default")
      (node (ref "U2") (pin "4") (pinfunction "PC15-OSC32_OUT_4") (pintype "bidirectional"))
    )
    (net (code "61") (name "unconnected-(U2-VBAT-Pad1)") (class "Default")
      (node (ref "U2") (pin "1") (pinfunction "VBAT_1") (pintype "power_in"))
    )
    (net (code "62") (name "unconnected-(U2-VDDA-Pad9)") (class "Default")
      (node (ref "U2") (pin "9") (pinfunction "VDDA_9") (pintype "power_in"))
    )
    (net (code "63") (name "unconnected-(U2-VSSA-Pad8)") (class "Default")
      (node (ref "U2") (pin "8") (pinfunction "VSSA_8") (pintype "power_in"))
    )
  )
)
